# MB1035.net
KiCad netlist of a schematic drawn in Altium Designer
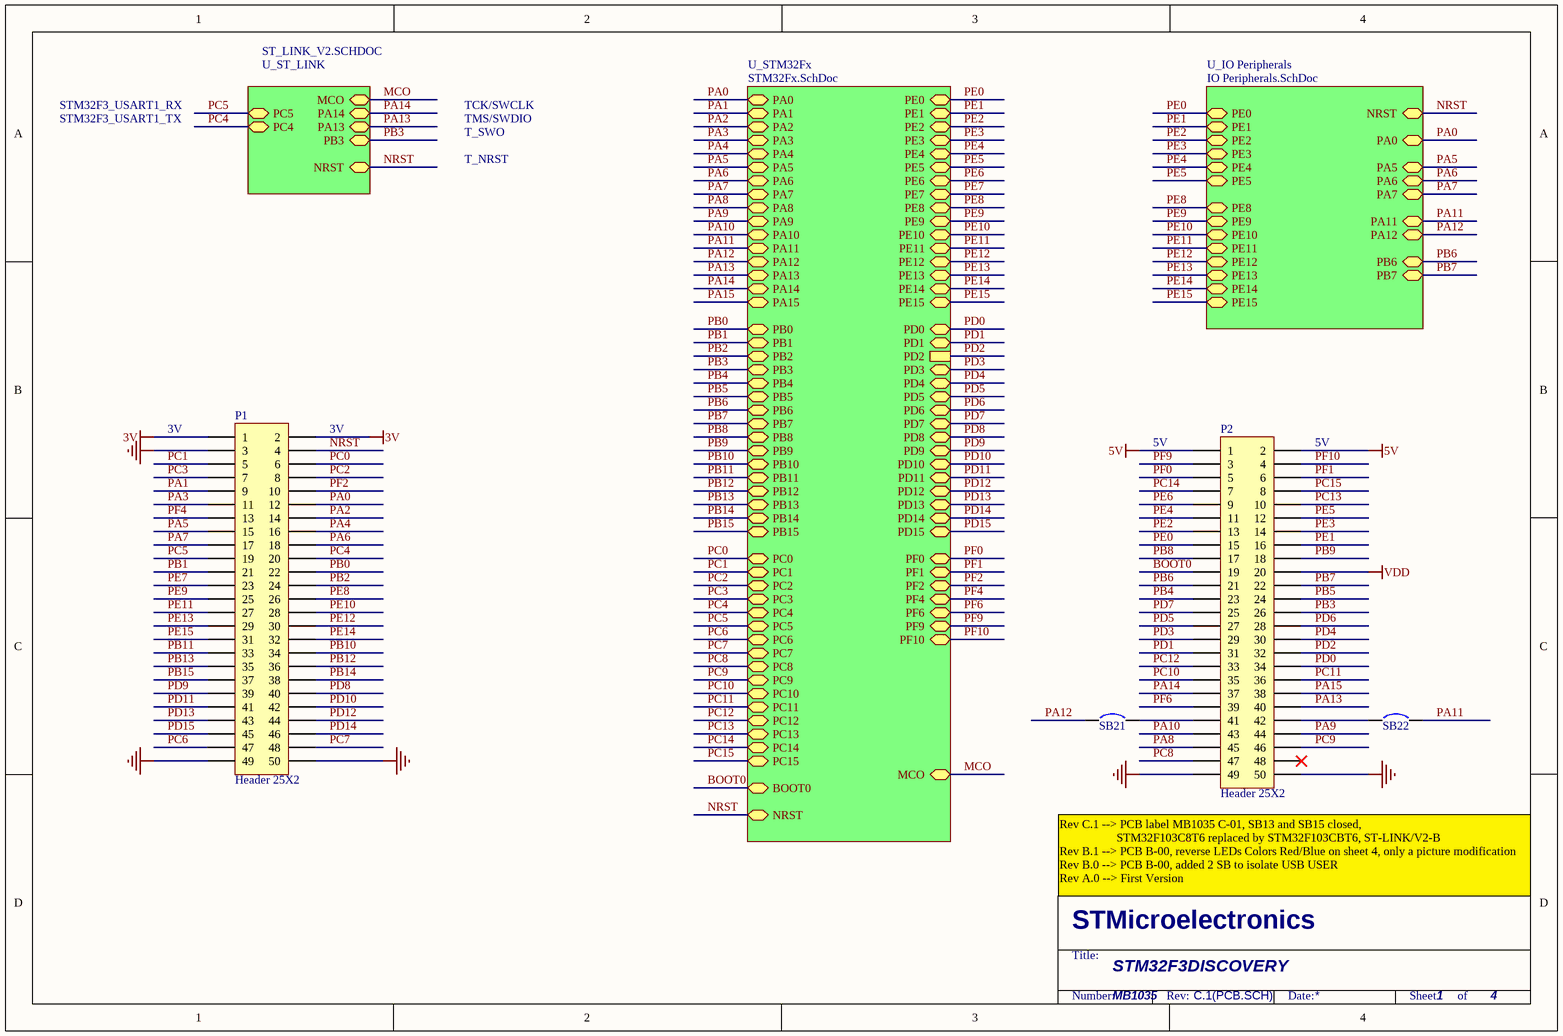
[diagram p0: MB1035.SchDoc]

(export (version "E")
  (design (tool "Eeschema 10.0.6"))
  (components
    (comp (ref "P1")
      (value "Header 25X2")
      (footprint "HEAD25X2/2.54")
      (description "Header, 25-Pin, Dual row")
      (fields (field (name "PUBLISHER") "Altium Limited"))
      (libsource (lib "Miscellaneous Connectors") (part "Header 25X2"))
    )
    (comp (ref "P2")
      (value "Header 25X2")
      (footprint "HEAD25X2/2.54")
      (description "Header, 25-Pin, Dual row")
      (fields (field (name "PUBLISHER") "Altium Limited"))
      (libsource (lib "Miscellaneous Connectors") (part "Header 25X2"))
    )
    (comp (ref "SB21")
      (value "Circuit Breaker")
      (footprint "JP2_SMD")
      (fields (field (name "PUBLISHER") "Altium Limited"))
      (libsource (lib "MB915") (part "Circuit Breaker"))
    )
    (comp (ref "SB22")
      (value "Circuit Breaker")
      (footprint "JP2_SMD")
      (fields (field (name "PUBLISHER") "Altium Limited"))
      (libsource (lib "MB915") (part "Circuit Breaker"))
    )
  )
  (nets
    (net (code "1") (name "/BOOT0") (class "Default")
      (node (ref "P2") (pin "19") (pinfunction "19_19") (pintype "passive"))
    )
    (net (code "3") (name "/NRST") (class "Default")
      (node (ref "P1") (pin "4") (pinfunction "4_4") (pintype "passive"))
    )
    (net (code "4") (name "/PA0") (class "Default")
      (node (ref "P1") (pin "12") (pinfunction "12_12") (pintype "passive"))
    )
    (net (code "5") (name "/PA1") (class "Default")
      (node (ref "P1") (pin "9") (pinfunction "9_9") (pintype "passive"))
    )
    (net (code "6") (name "/PA2") (class "Default")
      (node (ref "P1") (pin "14") (pinfunction "14_14") (pintype "passive"))
    )
    (net (code "7") (name "/PA3") (class "Default")
      (node (ref "P1") (pin "11") (pinfunction "11_11") (pintype "passive"))
    )
    (net (code "8") (name "/PA4") (class "Default")
      (node (ref "P1") (pin "16") (pinfunction "16_16") (pintype "passive"))
    )
    (net (code "9") (name "/PA5") (class "Default")
      (node (ref "P1") (pin "15") (pinfunction "15_15") (pintype "passive"))
    )
    (net (code "10") (name "/PA6") (class "Default")
      (node (ref "P1") (pin "18") (pinfunction "18_18") (pintype "passive"))
    )
    (net (code "11") (name "/PA7") (class "Default")
      (node (ref "P1") (pin "17") (pinfunction "17_17") (pintype "passive"))
    )
    (net (code "12") (name "/PA8") (class "Default")
      (node (ref "P2") (pin "45") (pinfunction "45_45") (pintype "passive"))
    )
    (net (code "13") (name "/PA9") (class "Default")
      (node (ref "P2") (pin "44") (pinfunction "44_44") (pintype "passive"))
    )
    (net (code "14") (name "/PA10") (class "Default")
      (node (ref "P2") (pin "43") (pinfunction "43_43") (pintype "passive"))
    )
    (net (code "15") (name "/PA11") (class "Default")
      (node (ref "SB22") (pin "2") (pinfunction "2_2") (pintype "passive"))
    )
    (net (code "16") (name "/PA12") (class "Default")
      (node (ref "SB21") (pin "1") (pinfunction "1_1") (pintype "passive"))
    )
    (net (code "17") (name "/PA13") (class "Default")
      (node (ref "P2") (pin "40") (pinfunction "40_40") (pintype "passive"))
    )
    (net (code "18") (name "/PA14") (class "Default")
      (node (ref "P2") (pin "37") (pinfunction "37_37") (pintype "passive"))
    )
    (net (code "19") (name "/PA15") (class "Default")
      (node (ref "P2") (pin "38") (pinfunction "38_38") (pintype "passive"))
    )
    (net (code "20") (name "/PB0") (class "Default")
      (node (ref "P1") (pin "22") (pinfunction "22_22") (pintype "passive"))
    )
    (net (code "21") (name "/PB1") (class "Default")
      (node (ref "P1") (pin "21") (pinfunction "21_21") (pintype "passive"))
    )
    (net (code "22") (name "/PB2") (class "Default")
      (node (ref "P1") (pin "24") (pinfunction "24_24") (pintype "passive"))
    )
    (net (code "23") (name "/PB3") (class "Default")
      (node (ref "P2") (pin "26") (pinfunction "26_26") (pintype "passive"))
    )
    (net (code "24") (name "/PB4") (class "Default")
      (node (ref "P2") (pin "23") (pinfunction "23_23") (pintype "passive"))
    )
    (net (code "25") (name "/PB5") (class "Default")
      (node (ref "P2") (pin "24") (pinfunction "24_24") (pintype "passive"))
    )
    (net (code "26") (name "/PB6") (class "Default")
      (node (ref "P2") (pin "21") (pinfunction "21_21") (pintype "passive"))
    )
    (net (code "27") (name "/PB7") (class "Default")
      (node (ref "P2") (pin "22") (pinfunction "22_22") (pintype "passive"))
    )
    (net (code "28") (name "/PB8") (class "Default")
      (node (ref "P2") (pin "17") (pinfunction "17_17") (pintype "passive"))
    )
    (net (code "29") (name "/PB9") (class "Default")
      (node (ref "P2") (pin "18") (pinfunction "18_18") (pintype "passive"))
    )
    (net (code "30") (name "/PB10") (class "Default")
      (node (ref "P1") (pin "34") (pinfunction "34_34") (pintype "passive"))
    )
    (net (code "31") (name "/PB11") (class "Default")
      (node (ref "P1") (pin "33") (pinfunction "33_33") (pintype "passive"))
    )
    (net (code "32") (name "/PB12") (class "Default")
      (node (ref "P1") (pin "36") (pinfunction "36_36") (pintype "passive"))
    )
    (net (code "33") (name "/PB13") (class "Default")
      (node (ref "P1") (pin "35") (pinfunction "35_35") (pintype "passive"))
    )
    (net (code "34") (name "/PB14") (class "Default")
      (node (ref "P1") (pin "38") (pinfunction "38_38") (pintype "passive"))
    )
    (net (code "35") (name "/PB15") (class "Default")
      (node (ref "P1") (pin "37") (pinfunction "37_37") (pintype "passive"))
    )
    (net (code "36") (name "/PC0") (class "Default")
      (node (ref "P1") (pin "6") (pinfunction "6_6") (pintype "passive"))
    )
    (net (code "37") (name "/PC1") (class "Default")
      (node (ref "P1") (pin "5") (pinfunction "5_5") (pintype "passive"))
    )
    (net (code "38") (name "/PC2") (class "Default")
      (node (ref "P1") (pin "8") (pinfunction "8_8") (pintype "passive"))
    )
    (net (code "39") (name "/PC3") (class "Default")
      (node (ref "P1") (pin "7") (pinfunction "7_7") (pintype "passive"))
    )
    (net (code "40") (name "/PC4") (class "Default")
      (node (ref "P1") (pin "20") (pinfunction "20_20") (pintype "passive"))
    )
    (net (code "41") (name "/PC5") (class "Default")
      (node (ref "P1") (pin "19") (pinfunction "19_19") (pintype "passive"))
    )
    (net (code "42") (name "/PC6") (class "Default")
      (node (ref "P1") (pin "47") (pinfunction "47_47") (pintype "passive"))
    )
    (net (code "43") (name "/PC7") (class "Default")
      (node (ref "P1") (pin "48") (pinfunction "48_48") (pintype "passive"))
    )
    (net (code "44") (name "/PC8") (class "Default")
      (node (ref "P2") (pin "47") (pinfunction "47_47") (pintype "passive"))
    )
    (net (code "45") (name "/PC9") (class "Default")
      (node (ref "P2") (pin "46") (pinfunction "46_46") (pintype "passive"))
    )
    (net (code "46") (name "/PC10") (class "Default")
      (node (ref "P2") (pin "35") (pinfunction "35_35") (pintype "passive"))
    )
    (net (code "47") (name "/PC11") (class "Default")
      (node (ref "P2") (pin "36") (pinfunction "36_36") (pintype "passive"))
    )
    (net (code "48") (name "/PC12") (class "Default")
      (node (ref "P2") (pin "33") (pinfunction "33_33") (pintype "passive"))
    )
    (net (code "49") (name "/PC13") (class "Default")
      (node (ref "P2") (pin "10") (pinfunction "10_10") (pintype "passive"))
    )
    (net (code "50") (name "/PC14") (class "Default")
      (node (ref "P2") (pin "7") (pinfunction "7_7") (pintype "passive"))
    )
    (net (code "51") (name "/PC15") (class "Default")
      (node (ref "P2") (pin "8") (pinfunction "8_8") (pintype "passive"))
    )
    (net (code "52") (name "/PD0") (class "Default")
      (node (ref "P2") (pin "34") (pinfunction "34_34") (pintype "passive"))
    )
    (net (code "53") (name "/PD1") (class "Default")
      (node (ref "P2") (pin "31") (pinfunction "31_31") (pintype "passive"))
    )
    (net (code "54") (name "/PD2") (class "Default")
      (node (ref "P2") (pin "32") (pinfunction "32_32") (pintype "passive"))
    )
    (net (code "55") (name "/PD3") (class "Default")
      (node (ref "P2") (pin "29") (pinfunction "29_29") (pintype "passive"))
    )
    (net (code "56") (name "/PD4") (class "Default")
      (node (ref "P2") (pin "30") (pinfunction "30_30") (pintype "passive"))
    )
    (net (code "57") (name "/PD5") (class "Default")
      (node (ref "P2") (pin "27") (pinfunction "27_27") (pintype "passive"))
    )
    (net (code "58") (name "/PD6") (class "Default")
      (node (ref "P2") (pin "28") (pinfunction "28_28") (pintype "passive"))
    )
    (net (code "59") (name "/PD7") (class "Default")
      (node (ref "P2") (pin "25") (pinfunction "25_25") (pintype "passive"))
    )
    (net (code "60") (name "/PD8") (class "Default")
      (node (ref "P1") (pin "40") (pinfunction "40_40") (pintype "passive"))
    )
    (net (code "61") (name "/PD9") (class "Default")
      (node (ref "P1") (pin "39") (pinfunction "39_39") (pintype "passive"))
    )
    (net (code "62") (name "/PD10") (class "Default")
      (node (ref "P1") (pin "42") (pinfunction "42_42") (pintype "passive"))
    )
    (net (code "63") (name "/PD11") (class "Default")
      (node (ref "P1") (pin "41") (pinfunction "41_41") (pintype "passive"))
    )
    (net (code "64") (name "/PD12") (class "Default")
      (node (ref "P1") (pin "44") (pinfunction "44_44") (pintype "passive"))
    )
    (net (code "65") (name "/PD13") (class "Default")
      (node (ref "P1") (pin "43") (pinfunction "43_43") (pintype "passive"))
    )
    (net (code "66") (name "/PD14") (class "Default")
      (node (ref "P1") (pin "46") (pinfunction "46_46") (pintype "passive"))
    )
    (net (code "67") (name "/PD15") (class "Default")
      (node (ref "P1") (pin "45") (pinfunction "45_45") (pintype "passive"))
    )
    (net (code "68") (name "/PE0") (class "Default")
      (node (ref "P2") (pin "15") (pinfunction "15_15") (pintype "passive"))
    )
    (net (code "69") (name "/PE1") (class "Default")
      (node (ref "P2") (pin "16") (pinfunction "16_16") (pintype "passive"))
    )
    (net (code "70") (name "/PE2") (class "Default")
      (node (ref "P2") (pin "13") (pinfunction "13_13") (pintype "passive"))
    )
    (net (code "71") (name "/PE3") (class "Default")
      (node (ref "P2") (pin "14") (pinfunction "14_14") (pintype "passive"))
    )
    (net (code "72") (name "/PE4") (class "Default")
      (node (ref "P2") (pin "11") (pinfunction "11_11") (pintype "passive"))
    )
    (net (code "73") (name "/PE5") (class "Default")
      (node (ref "P2") (pin "12") (pinfunction "12_12") (pintype "passive"))
    )
    (net (code "74") (name "/PE6") (class "Default")
      (node (ref "P2") (pin "9") (pinfunction "9_9") (pintype "passive"))
    )
    (net (code "75") (name "/PE7") (class "Default")
      (node (ref "P1") (pin "23") (pinfunction "23_23") (pintype "passive"))
    )
    (net (code "76") (name "/PE8") (class "Default")
      (node (ref "P1") (pin "26") (pinfunction "26_26") (pintype "passive"))
    )
    (net (code "77") (name "/PE9") (class "Default")
      (node (ref "P1") (pin "25") (pinfunction "25_25") (pintype "passive"))
    )
    (net (code "78") (name "/PE10") (class "Default")
      (node (ref "P1") (pin "28") (pinfunction "28_28") (pintype "passive"))
    )
    (net (code "79") (name "/PE11") (class "Default")
      (node (ref "P1") (pin "27") (pinfunction "27_27") (pintype "passive"))
    )
    (net (code "80") (name "/PE12") (class "Default")
      (node (ref "P1") (pin "30") (pinfunction "30_30") (pintype "passive"))
    )
    (net (code "81") (name "/PE13") (class "Default")
      (node (ref "P1") (pin "29") (pinfunction "29_29") (pintype "passive"))
    )
    (net (code "82") (name "/PE14") (class "Default")
      (node (ref "P1") (pin "32") (pinfunction "32_32") (pintype "passive"))
    )
    (net (code "83") (name "/PE15") (class "Default")
      (node (ref "P1") (pin "31") (pinfunction "31_31") (pintype "passive"))
    )
    (net (code "84") (name "/PF0") (class "Default")
      (node (ref "P2") (pin "5") (pinfunction "5_5") (pintype "passive"))
    )
    (net (code "85") (name "/PF1") (class "Default")
      (node (ref "P2") (pin "6") (pinfunction "6_6") (pintype "passive"))
    )
    (net (code "86") (name "/PF2") (class "Default")
      (node (ref "P1") (pin "10") (pinfunction "10_10") (pintype "passive"))
    )
    (net (code "87") (name "/PF4") (class "Default")
      (node (ref "P1") (pin "13") (pinfunction "13_13") (pintype "passive"))
    )
    (net (code "88") (name "/PF6") (class "Default")
      (node (ref "P2") (pin "39") (pinfunction "39_39") (pintype "passive"))
    )
    (net (code "89") (name "/PF9") (class "Default")
      (node (ref "P2") (pin "3") (pinfunction "3_3") (pintype "passive"))
    )
    (net (code "90") (name "/PF10") (class "Default")
      (node (ref "P2") (pin "4") (pinfunction "4_4") (pintype "passive"))
    )
    (net (code "91") (name "3V") (class "Default")
      (node (ref "P1") (pin "1") (pinfunction "1_1") (pintype "passive"))
      (node (ref "P1") (pin "2") (pinfunction "2_2") (pintype "passive"))
    )
    (net (code "92") (name "5V") (class "Default")
      (node (ref "P2") (pin "1") (pinfunction "1_1") (pintype "passive"))
      (node (ref "P2") (pin "2") (pinfunction "2_2") (pintype "passive"))
    )
    (net (code "93") (name "GND") (class "Default")
      (node (ref "P1") (pin "3") (pinfunction "3_3") (pintype "passive"))
      (node (ref "P1") (pin "49") (pinfunction "49_49") (pintype "passive"))
      (node (ref "P1") (pin "50") (pinfunction "50_50") (pintype "passive"))
      (node (ref "P2") (pin "49") (pinfunction "49_49") (pintype "passive"))
      (node (ref "P2") (pin "50") (pinfunction "50_50") (pintype "passive"))
    )
    (net (code "94") (name "Net-(P2-Pad41)") (class "Default")
      (node (ref "P2") (pin "41") (pinfunction "41_41") (pintype "passive"))
      (node (ref "SB21") (pin "2") (pinfunction "2_2") (pintype "passive"))
    )
    (net (code "95") (name "Net-(P2-Pad42)") (class "Default")
      (node (ref "P2") (pin "42") (pinfunction "42_42") (pintype "passive"))
      (node (ref "SB22") (pin "1") (pinfunction "1_1") (pintype "passive"))
    )
    (net (code "96") (name "VDD") (class "Default")
      (node (ref "P2") (pin "20") (pinfunction "20_20") (pintype "passive"))
    )
    (net (code "97") (name "unconnected-(P2-Pad48)") (class "Default")
      (node (ref "P2") (pin "48") (pinfunction "48_48") (pintype "passive+no_connect"))
    )
  )
)
